# Precharge_circuit.net
KiCad netlist of a schematic drawn in Altium Designer
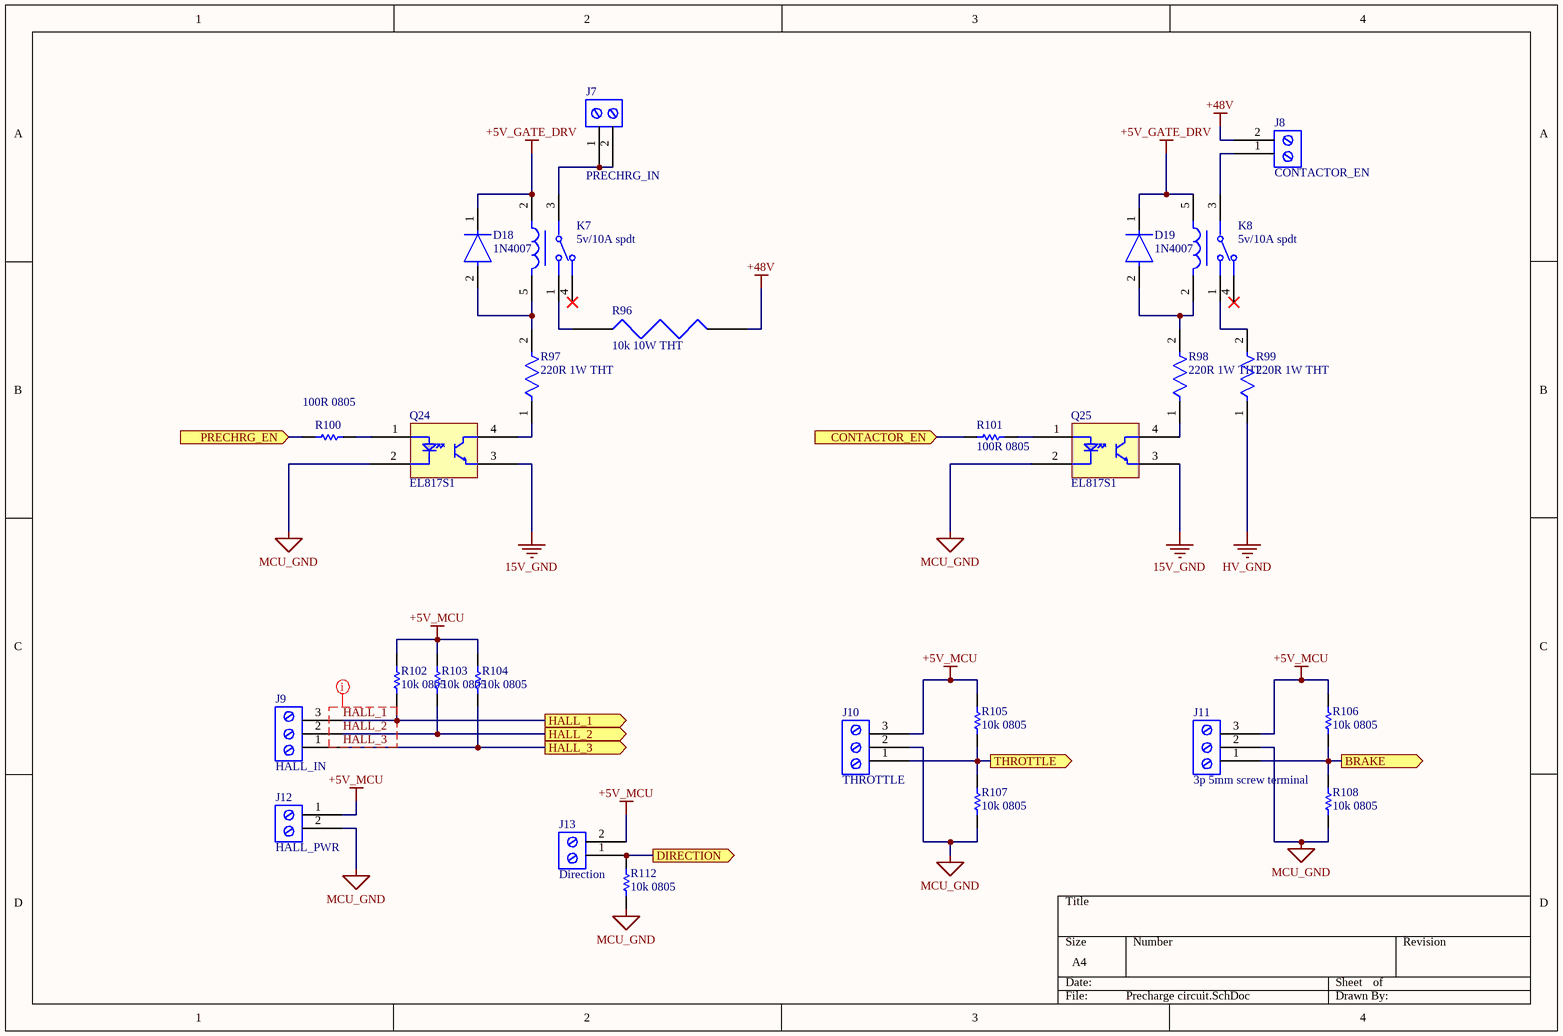
[diagram p0: Precharge circuit.SchDoc]

(export (version "E")
  (design (tool "Eeschema 10.0.6"))
  (components
    (comp (ref "D18")
      (value "1N4007")
      (footprint "FP-1N4007-MFG")
      (description "GOOD-ARK 1N4007 General Purpose Rectifier Diode – DO-41 Package")
      (fields
        (field (name "MANUFACTURER") "Diotec")
        (field (name "OCTOPART") "https://octopart.com/1n4007-diotec-4040411")
      )
      (libsource (lib "Altium Content Vault") (part "d7152d700b627762746794eb795d46e"))
    )
    (comp (ref "D19")
      (value "1N4007")
      (footprint "FP-1N4007-MFG")
      (description "GOOD-ARK 1N4007 General Purpose Rectifier Diode – DO-41 Package")
      (fields
        (field (name "MANUFACTURER") "Diotec")
        (field (name "OCTOPART") "https://octopart.com/1n4007-diotec-4040411")
      )
      (libsource (lib "Altium Content Vault") (part "d7152d700b627762746794eb795d46e"))
    )
    (comp (ref "J7")
      (value "PRECHRG_IN")
      (footprint "TERMINAL_5MM_2P")
      (description "XY127- 2 Pin Screw Terminal- 5mm Pitch")
      (libsource (lib "1kW_BLDC_Controller") (part "2p 5mm screw terminal"))
    )
    (comp (ref "J8")
      (value "CONTACTOR_EN")
      (footprint "TERMINAL_5MM_2P")
      (description "XY127- 2 Pin Screw Terminal- 5mm Pitch")
      (libsource (lib "1kW_BLDC_Controller") (part "2p 5mm screw terminal"))
    )
    (comp (ref "J9")
      (value "HALL_IN")
      (footprint "TERMINAL_5MM_3P")
      (description "XY127- 3 Pin Screw Terminal- 5mm Pitch")
      (libsource (lib "1kW_BLDC_Controller") (part "3p 5mm screw terminal"))
    )
    (comp (ref "J10")
      (value "THROTTLE")
      (footprint "TERMINAL_5MM_3P")
      (description "XY127- 3 Pin Screw Terminal- 5mm Pitch")
      (libsource (lib "1kW_BLDC_Controller") (part "3p 5mm screw terminal"))
    )
    (comp (ref "J11")
      (value "3p 5mm screw terminal")
      (footprint "TERMINAL_5MM_3P")
      (description "XY127- 3 Pin Screw Terminal- 5mm Pitch")
      (libsource (lib "1kW_BLDC_Controller") (part "3p 5mm screw terminal"))
    )
    (comp (ref "J12")
      (value "HALL_PWR")
      (footprint "TERMINAL_5MM_2P")
      (description "XY127- 2 Pin Screw Terminal- 5mm Pitch")
      (libsource (lib "") (part "2p 5mm screw terminal_2"))
    )
    (comp (ref "J13")
      (value "Direction")
      (footprint "TERMINAL_5MM_2P")
      (description "XY127- 2 Pin Screw Terminal- 5mm Pitch")
      (libsource (lib "") (part "2p 5mm screw terminal_1"))
    )
    (comp (ref "K7")
      (value "5v/10A spdt")
      (footprint "FP-G5LE-1-E-36-DC5-MFG")
      (description "HF3FF/005-1ZST – 05V 10A SPDT Relay – Hongfa")
      (libsource (lib "Altium Content Vault") (part "c03b8d08e5d02e70a6880f365e34168"))
    )
    (comp (ref "K8")
      (value "5v/10A spdt")
      (footprint "FP-G5LE-1-E-36-DC5-MFG")
      (description "HF3FF/005-1ZST – 05V 10A SPDT Relay – Hongfa")
      (libsource (lib "") (part "c03b8d08e5d02e70a6880f365e34168_1"))
    )
    (comp (ref "Q24")
      (value "EL817S1")
      (footprint "EL817S1")
      (description "EL817S1 (B) (TU) – F Optocoupler SMD-4 Cut Tape")
      (libsource (lib "1kW_BLDC_Controller") (part "EL817S1"))
    )
    (comp (ref "Q25")
      (value "EL817S1")
      (footprint "EL817S1")
      (description "EL817S1 (B) (TU) – F Optocoupler SMD-4 Cut Tape")
      (libsource (lib "1kW_BLDC_Controller") (part "EL817S1"))
    )
    (comp (ref "R96")
      (value "10k 10W THT")
      (footprint "R10W")
      (description "10K ohm 10W Fusible Cement Resistor")
      (libsource (lib "1kW_BLDC_Controller") (part "10k_10W_THT"))
    )
    (comp (ref "R97")
      (value "220R 1W THT")
      (footprint "R1WTHT")
      (description "220 Ohm 1 Watt Resistor 5% Tolerance")
      (libsource (lib "1kW_BLDC_Controller") (part "220R 1W THT"))
    )
    (comp (ref "R98")
      (value "220R 1W THT")
      (footprint "R1WTHT")
      (description "220 Ohm 1 Watt Resistor 5% Tolerance")
      (libsource (lib "1kW_BLDC_Controller") (part "220R 1W THT"))
    )
    (comp (ref "R99")
      (value "220R 1W THT")
      (footprint "R1WTHT")
      (description "220 Ohm 1 Watt Resistor 5% Tolerance")
      (libsource (lib "1kW_BLDC_Controller") (part "220R 1W THT"))
    )
    (comp (ref "R100")
      (value "100R 0805")
      (footprint "R0805")
      (description "100 ohm 1/4W Resistor 0805 Package")
      (libsource (lib "1kW_BLDC_Controller") (part "100R 0805"))
    )
    (comp (ref "R101")
      (value "100R 0805")
      (footprint "R0805")
      (description "100 ohm 1/4W Resistor 0805 Package")
      (libsource (lib "1kW_BLDC_Controller") (part "100R 0805"))
    )
    (comp (ref "R102")
      (value "10k 0805")
      (footprint "R0805")
      (description "10K Ohm 1/8 Watt Resistor 1% Tolerance RC0805FR-0710KL – 0805 Package")
      (libsource (lib "1kW_BLDC_Controller") (part "10k 0805"))
    )
    (comp (ref "R103")
      (value "10k 0805")
      (footprint "R0805")
      (description "10K Ohm 1/8 Watt Resistor 1% Tolerance RC0805FR-0710KL – 0805 Package")
      (libsource (lib "1kW_BLDC_Controller") (part "10k 0805"))
    )
    (comp (ref "R104")
      (value "10k 0805")
      (footprint "R0805")
      (description "10K Ohm 1/8 Watt Resistor 1% Tolerance RC0805FR-0710KL – 0805 Package")
      (libsource (lib "1kW_BLDC_Controller") (part "10k 0805"))
    )
    (comp (ref "R105")
      (value "10k 0805")
      (footprint "R0805")
      (description "10K Ohm 1/8 Watt Resistor 1% Tolerance RC0805FR-0710KL – 0805 Package")
      (libsource (lib "1kW_BLDC_Controller") (part "10k 0805"))
    )
    (comp (ref "R106")
      (value "10k 0805")
      (footprint "R0805")
      (description "10K Ohm 1/8 Watt Resistor 1% Tolerance RC0805FR-0710KL – 0805 Package")
      (libsource (lib "1kW_BLDC_Controller") (part "10k 0805"))
    )
    (comp (ref "R107")
      (value "10k 0805")
      (footprint "R0805")
      (description "10K Ohm 1/8 Watt Resistor 1% Tolerance RC0805FR-0710KL – 0805 Package")
      (libsource (lib "1kW_BLDC_Controller") (part "10k 0805"))
    )
    (comp (ref "R108")
      (value "10k 0805")
      (footprint "R0805")
      (description "10K Ohm 1/8 Watt Resistor 1% Tolerance RC0805FR-0710KL – 0805 Package")
      (libsource (lib "1kW_BLDC_Controller") (part "10k 0805"))
    )
    (comp (ref "R112")
      (value "10k 0805")
      (footprint "R0805")
      (description "10K Ohm 1/8 Watt Resistor 1% Tolerance RC0805FR-0710KL – 0805 Package")
      (libsource (lib "1kW_BLDC_Controller") (part "10k 0805"))
    )
  )
  (nets
    (net (code "1") (name "+5V_GATE_DRV") (class "Default")
      (node (ref "D18") (pin "1") (pinfunction "C_1") (pintype "passive"))
      (node (ref "D19") (pin "1") (pinfunction "C_1") (pintype "passive"))
      (node (ref "K7") (pin "2") (pinfunction "2_2") (pintype "passive"))
      (node (ref "K8") (pin "5") (pinfunction "2_5") (pintype "passive"))
    )
    (net (code "2") (name "+5V_MCU") (class "Default")
      (node (ref "J10") (pin "3") (pinfunction "3_3") (pintype "passive"))
      (node (ref "J11") (pin "3") (pinfunction "3_3") (pintype "passive"))
      (node (ref "J12") (pin "1") (pinfunction "2_1") (pintype "passive"))
      (node (ref "J13") (pin "2") (pinfunction "2_2") (pintype "passive"))
      (node (ref "R102") (pin "2") (pinfunction "2_2") (pintype "passive"))
      (node (ref "R103") (pin "2") (pinfunction "2_2") (pintype "passive"))
      (node (ref "R104") (pin "2") (pinfunction "2_2") (pintype "passive"))
      (node (ref "R105") (pin "2") (pinfunction "2_2") (pintype "passive"))
      (node (ref "R106") (pin "2") (pinfunction "2_2") (pintype "passive"))
    )
    (net (code "3") (name "+48V") (class "Default")
      (node (ref "J8") (pin "2") (pinfunction "2_2") (pintype "passive"))
      (node (ref "R96") (pin "2") (pinfunction "2_2") (pintype "passive"))
    )
    (net (code "4") (name "/BRAKE") (class "Default")
      (node (ref "J11") (pin "1") (pinfunction "1_1") (pintype "passive"))
      (node (ref "R106") (pin "1") (pinfunction "1_1") (pintype "passive"))
      (node (ref "R108") (pin "2") (pinfunction "2_2") (pintype "passive"))
    )
    (net (code "5") (name "/CONTACTOR_EN") (class "Default")
      (node (ref "R101") (pin "1") (pinfunction "1_1") (pintype "passive"))
    )
    (net (code "6") (name "/DIRECTION") (class "Default")
      (node (ref "J13") (pin "1") (pinfunction "1_1") (pintype "passive"))
      (node (ref "R112") (pin "2") (pinfunction "2_2") (pintype "passive"))
    )
    (net (code "7") (name "/HALL_1") (class "Default")
      (node (ref "J9") (pin "3") (pinfunction "3_3") (pintype "passive"))
      (node (ref "R102") (pin "1") (pinfunction "1_1") (pintype "passive"))
    )
    (net (code "8") (name "/HALL_2") (class "Default")
      (node (ref "J9") (pin "2") (pinfunction "2_2") (pintype "passive"))
      (node (ref "R103") (pin "1") (pinfunction "1_1") (pintype "passive"))
    )
    (net (code "9") (name "/HALL_3") (class "Default")
      (node (ref "J9") (pin "1") (pinfunction "1_1") (pintype "passive"))
      (node (ref "R104") (pin "1") (pinfunction "1_1") (pintype "passive"))
    )
    (net (code "10") (name "/PRECHRG_EN") (class "Default")
      (node (ref "R100") (pin "1") (pinfunction "1_1") (pintype "passive"))
    )
    (net (code "11") (name "/THROTTLE") (class "Default")
      (node (ref "J10") (pin "1") (pinfunction "1_1") (pintype "passive"))
      (node (ref "R105") (pin "1") (pinfunction "1_1") (pintype "passive"))
      (node (ref "R107") (pin "2") (pinfunction "2_2") (pintype "passive"))
    )
    (net (code "12") (name "15V_GND") (class "Default")
      (node (ref "Q24") (pin "3") (pinfunction "E_3") (pintype "passive"))
      (node (ref "Q25") (pin "3") (pinfunction "E_3") (pintype "passive"))
    )
    (net (code "13") (name "HV_GND") (class "Default")
      (node (ref "R99") (pin "1") (pinfunction "1_1") (pintype "passive"))
    )
    (net (code "14") (name "MCU_GND") (class "Default")
      (node (ref "J10") (pin "2") (pinfunction "2_2") (pintype "passive"))
      (node (ref "J11") (pin "2") (pinfunction "2_2") (pintype "passive"))
      (node (ref "J12") (pin "2") (pinfunction "1_2") (pintype "passive"))
      (node (ref "Q24") (pin "2") (pinfunction "K_2") (pintype "passive"))
      (node (ref "Q25") (pin "2") (pinfunction "K_2") (pintype "passive"))
      (node (ref "R107") (pin "1") (pinfunction "1_1") (pintype "passive"))
      (node (ref "R108") (pin "1") (pinfunction "1_1") (pintype "passive"))
      (node (ref "R112") (pin "1") (pinfunction "1_1") (pintype "passive"))
    )
    (net (code "15") (name "Net-(D18-A)") (class "Default")
      (node (ref "D18") (pin "2") (pinfunction "A_2") (pintype "passive"))
      (node (ref "K7") (pin "5") (pinfunction "5_5") (pintype "passive"))
      (node (ref "R97") (pin "2") (pinfunction "2_2") (pintype "passive"))
    )
    (net (code "16") (name "Net-(D19-A)") (class "Default")
      (node (ref "D19") (pin "2") (pinfunction "A_2") (pintype "passive"))
      (node (ref "K8") (pin "2") (pinfunction "5_2") (pintype "passive"))
      (node (ref "R98") (pin "2") (pinfunction "2_2") (pintype "passive"))
    )
    (net (code "17") (name "Net-(K7-1)") (class "Default")
      (node (ref "J7") (pin "1") (pinfunction "1_1") (pintype "passive"))
      (node (ref "J7") (pin "2") (pinfunction "2_2") (pintype "passive"))
      (node (ref "K7") (pin "3") (pinfunction "1_3") (pintype "passive"))
    )
    (net (code "18") (name "Net-(K7-3)") (class "Default")
      (node (ref "K7") (pin "1") (pinfunction "3_1") (pintype "passive"))
      (node (ref "R96") (pin "1") (pinfunction "1_1") (pintype "passive"))
    )
    (net (code "19") (name "Net-(K8-1)") (class "Default")
      (node (ref "J8") (pin "1") (pinfunction "1_1") (pintype "passive"))
      (node (ref "K8") (pin "3") (pinfunction "1_3") (pintype "passive"))
    )
    (net (code "20") (name "Net-(K8-3)") (class "Default")
      (node (ref "K8") (pin "1") (pinfunction "3_1") (pintype "passive"))
      (node (ref "R99") (pin "2") (pinfunction "2_2") (pintype "passive"))
    )
    (net (code "21") (name "Net-(Q24-A)") (class "Default")
      (node (ref "Q24") (pin "1") (pinfunction "A_1") (pintype "passive"))
      (node (ref "R100") (pin "2") (pinfunction "2_2") (pintype "passive"))
    )
    (net (code "22") (name "Net-(Q24-C)") (class "Default")
      (node (ref "Q24") (pin "4") (pinfunction "C_4") (pintype "passive"))
      (node (ref "R97") (pin "1") (pinfunction "1_1") (pintype "passive"))
    )
    (net (code "23") (name "Net-(Q25-A)") (class "Default")
      (node (ref "Q25") (pin "1") (pinfunction "A_1") (pintype "passive"))
      (node (ref "R101") (pin "2") (pinfunction "2_2") (pintype "passive"))
    )
    (net (code "24") (name "Net-(Q25-C)") (class "Default")
      (node (ref "Q25") (pin "4") (pinfunction "C_4") (pintype "passive"))
      (node (ref "R98") (pin "1") (pinfunction "1_1") (pintype "passive"))
    )
    (net (code "25") (name "unconnected-(K7-Pad4)") (class "Default")
      (node (ref "K7") (pin "4") (pinfunction "4_4") (pintype "passive+no_connect"))
    )
    (net (code "26") (name "unconnected-(K8-Pad4)") (class "Default")
      (node (ref "K8") (pin "4") (pinfunction "4_4") (pintype "passive+no_connect"))
    )
  )
)
